# Sensorboard.net
KiCad netlist of a schematic drawn in EAGLE
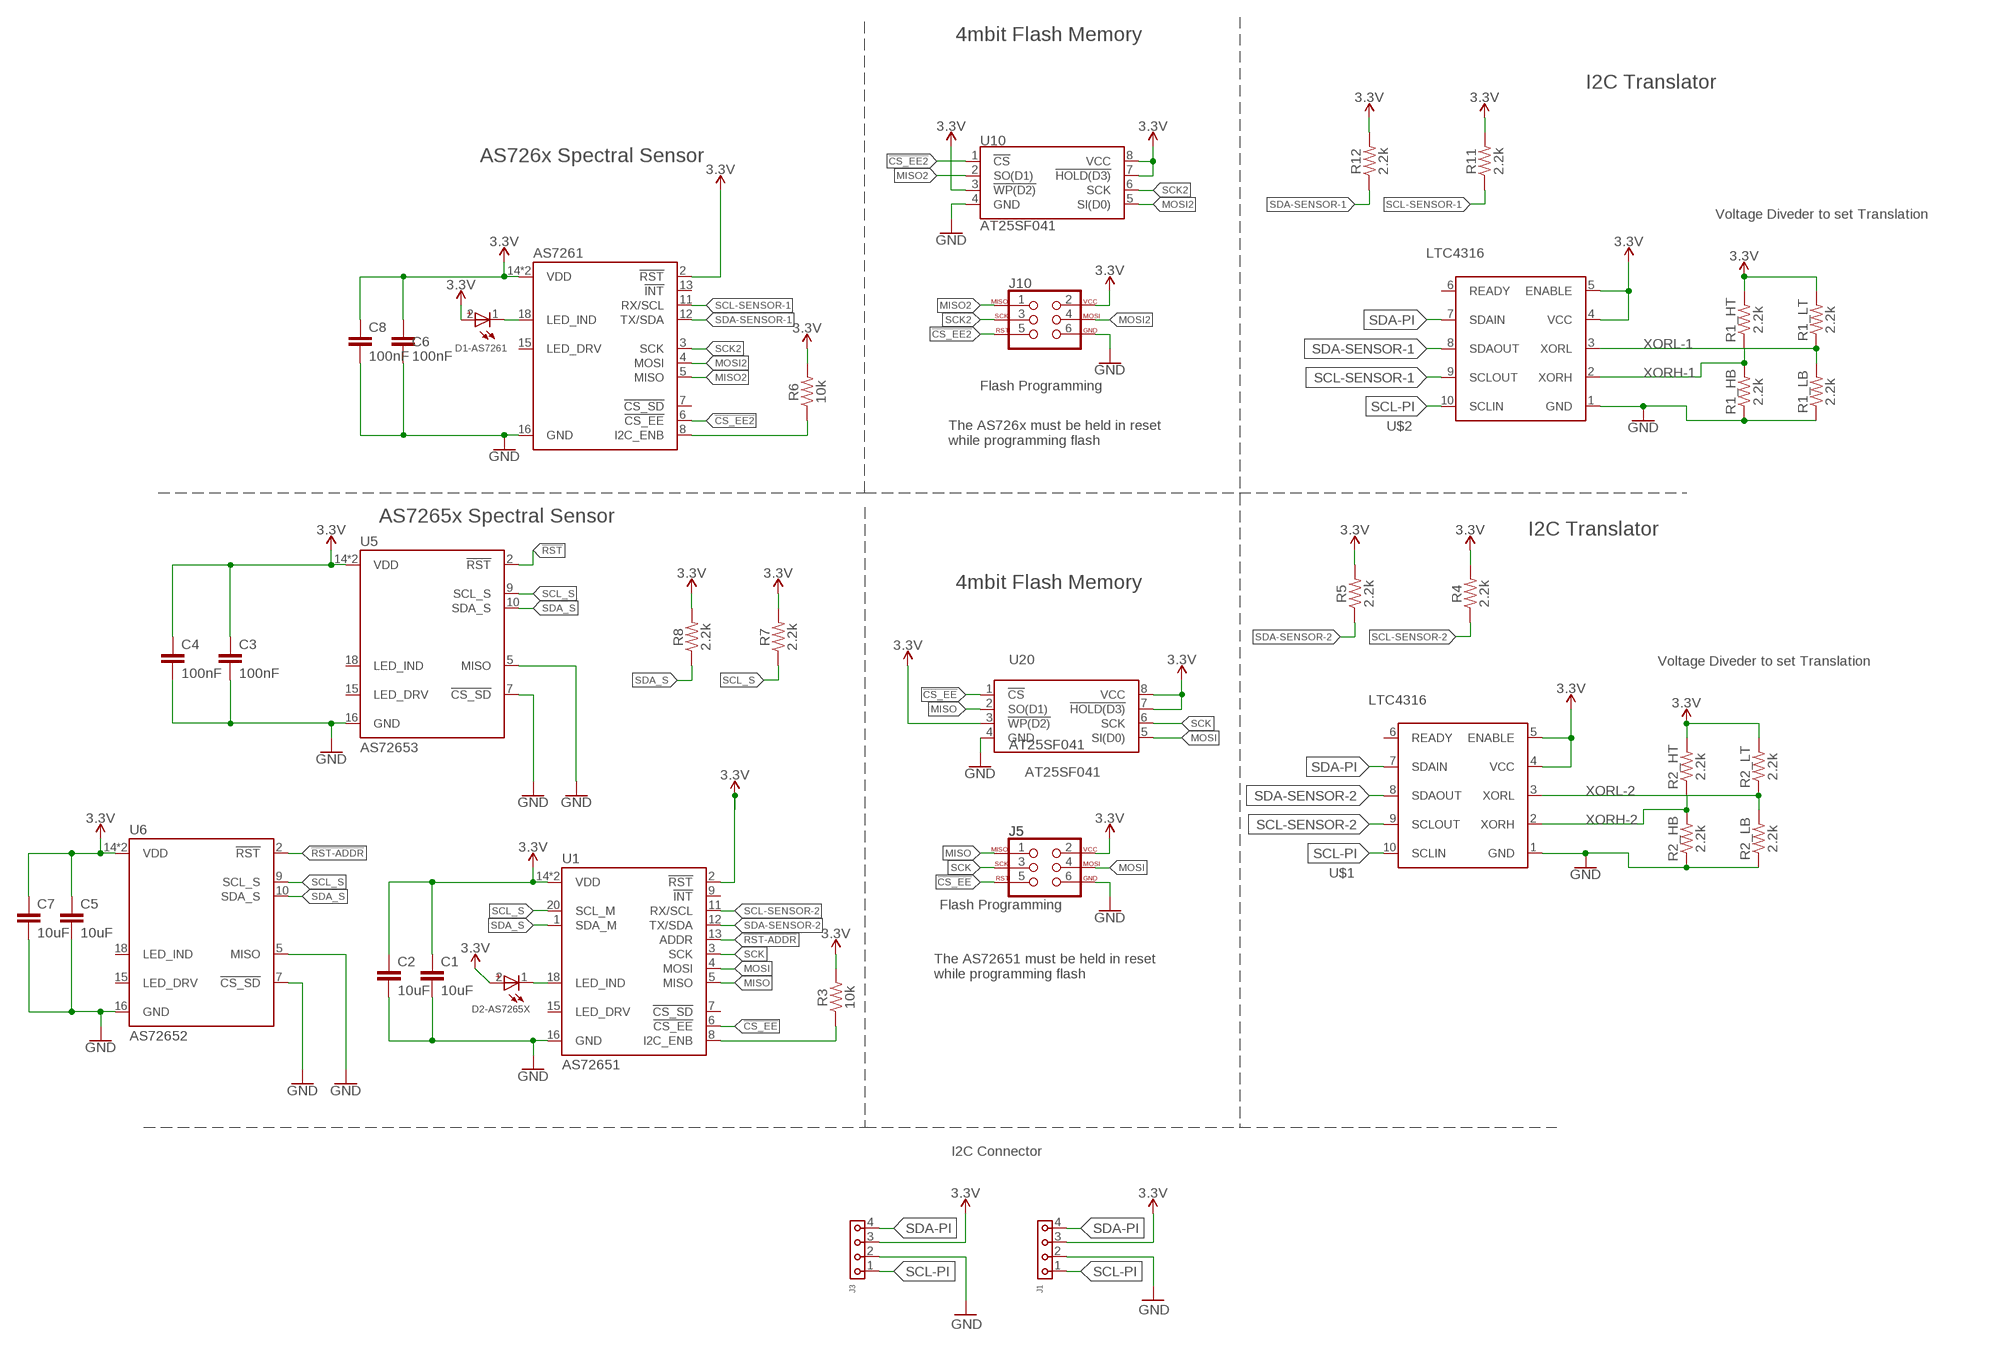
[diagram p0: schematic, sheet 1]

(export (version "E")
  (design (tool "Eeschema 10.0.6"))
  (components
    (comp (ref "AS7261")
      (value "IR")
      (footprint "eagle-import:LGA20")
      (libsource (lib "eagle-import") (part "AS726XIR"))
    )
    (comp (ref "C1")
      (value "10uF")
      (footprint "eagle-import:0603")
      (libsource (lib "eagle-import") (part "1.0UF-0603-16V-10%"))
    )
    (comp (ref "C2")
      (value "10uF")
      (footprint "eagle-import:0603")
      (libsource (lib "eagle-import") (part "10UF-0603-6.3V-20%"))
    )
    (comp (ref "C3")
      (value "100nF")
      (footprint "eagle-import:0603")
      (libsource (lib "eagle-import") (part "1.0UF-0603-16V-10%"))
    )
    (comp (ref "C4")
      (value "100nF")
      (footprint "eagle-import:0603")
      (libsource (lib "eagle-import") (part "10UF-0603-6.3V-20%"))
    )
    (comp (ref "C5")
      (value "10uF")
      (footprint "eagle-import:0603")
      (libsource (lib "eagle-import") (part "1.0UF-0603-16V-10%"))
    )
    (comp (ref "C6")
      (value "100nF")
      (footprint "eagle-import:0603")
      (libsource (lib "eagle-import") (part "1.0UF-0603-16V-10%"))
    )
    (comp (ref "C7")
      (value "10uF")
      (footprint "eagle-import:0603")
      (libsource (lib "eagle-import") (part "10UF-0603-6.3V-20%"))
    )
    (comp (ref "C8")
      (value "100nF")
      (footprint "eagle-import:0603")
      (libsource (lib "eagle-import") (part "10UF-0603-6.3V-20%"))
    )
    (comp (ref "D1-AS7261")
      (value "WL-SMCW_1206_150120RS75000")
      (footprint "eagle-import:WL-SMCW_1206")
      (libsource (lib "eagle-import") (part "WL-SMCW_1206_150120RS75000"))
    )
    (comp (ref "D2-AS7265X")
      (value "WL-SMCW_1206_150120RS75000")
      (footprint "eagle-import:WL-SMCW_1206")
      (libsource (lib "eagle-import") (part "WL-SMCW_1206_150120RS75000"))
    )
    (comp (ref "J1")
      (value "6130XX11821_61300411821")
      (footprint "eagle-import:61300411821")
      (libsource (lib "eagle-import") (part "6130XX11821_61300411821"))
    )
    (comp (ref "J3")
      (value "6130XX11821_61300411821")
      (footprint "eagle-import:61300411821")
      (libsource (lib "eagle-import") (part "6130XX11821_61300411821"))
    )
    (comp (ref "J5")
      (value "Flash Programming")
      (footprint "eagle-import:2X3_TEST_POINTS")
      (libsource (lib "eagle-import") (part "AVR_SPI_PROG_3X2TESTPOINTS"))
    )
    (comp (ref "J10")
      (value "Flash Programming")
      (footprint "eagle-import:2X3_TEST_POINTS")
      (libsource (lib "eagle-import") (part "AVR_SPI_PROG_3X2TESTPOINTS"))
    )
    (comp (ref "R1_HB")
      (value "2.2k")
      (footprint "eagle-import:0603")
      (libsource (lib "eagle-import") (part "2.2KOHM-0603-1/10W-1%"))
    )
    (comp (ref "R1_HT")
      (value "2.2k")
      (footprint "eagle-import:0603")
      (libsource (lib "eagle-import") (part "2.2KOHM-0603-1/10W-1%"))
    )
    (comp (ref "R1_LB")
      (value "2.2k")
      (footprint "eagle-import:0603")
      (libsource (lib "eagle-import") (part "2.2KOHM-0603-1/10W-1%"))
    )
    (comp (ref "R1_LT")
      (value "2.2k")
      (footprint "eagle-import:0603")
      (libsource (lib "eagle-import") (part "2.2KOHM-0603-1/10W-1%"))
    )
    (comp (ref "R2_HB")
      (value "2.2k")
      (footprint "eagle-import:0603")
      (libsource (lib "eagle-import") (part "2.2KOHM-0603-1/10W-1%"))
    )
    (comp (ref "R2_HT")
      (value "2.2k")
      (footprint "eagle-import:0603")
      (libsource (lib "eagle-import") (part "2.2KOHM-0603-1/10W-1%"))
    )
    (comp (ref "R2_LB")
      (value "2.2k")
      (footprint "eagle-import:0603")
      (libsource (lib "eagle-import") (part "2.2KOHM-0603-1/10W-1%"))
    )
    (comp (ref "R2_LT")
      (value "2.2k")
      (footprint "eagle-import:0603")
      (libsource (lib "eagle-import") (part "2.2KOHM-0603-1/10W-1%"))
    )
    (comp (ref "R3")
      (value "10k")
      (footprint "eagle-import:0603")
      (libsource (lib "eagle-import") (part "10KOHM-0603-1/10W-1%"))
    )
    (comp (ref "R4")
      (value "2.2k")
      (footprint "eagle-import:0603")
      (libsource (lib "eagle-import") (part "2.2KOHM-0603-1/10W-1%"))
    )
    (comp (ref "R5")
      (value "2.2k")
      (footprint "eagle-import:0603")
      (libsource (lib "eagle-import") (part "2.2KOHM-0603-1/10W-1%"))
    )
    (comp (ref "R6")
      (value "10k")
      (footprint "eagle-import:0603")
      (libsource (lib "eagle-import") (part "10KOHM-0603-1/10W-1%"))
    )
    (comp (ref "R7")
      (value "2.2k")
      (footprint "eagle-import:0603")
      (libsource (lib "eagle-import") (part "2.2KOHM-0603-1/10W-1%"))
    )
    (comp (ref "R8")
      (value "2.2k")
      (footprint "eagle-import:0603")
      (libsource (lib "eagle-import") (part "2.2KOHM-0603-1/10W-1%"))
    )
    (comp (ref "R11")
      (value "2.2k")
      (footprint "eagle-import:0603")
      (libsource (lib "eagle-import") (part "2.2KOHM-0603-1/10W-1%"))
    )
    (comp (ref "R12")
      (value "2.2k")
      (footprint "eagle-import:0603")
      (libsource (lib "eagle-import") (part "2.2KOHM-0603-1/10W-1%"))
    )
    (comp (ref "U$1")
      (value "LTC4316")
      (footprint "eagle-import:MS-PACKAGE")
      (libsource (lib "eagle-import") (part "LTC4316"))
    )
    (comp (ref "U$2")
      (value "LTC4316")
      (footprint "eagle-import:MS-PACKAGE")
      (libsource (lib "eagle-import") (part "LTC4316"))
    )
    (comp (ref "U1")
      (value "AS72651")
      (footprint "eagle-import:LGA20")
      (libsource (lib "eagle-import") (part "AS72651"))
    )
    (comp (ref "U5")
      (value "AS72653")
      (footprint "eagle-import:LGA20")
      (libsource (lib "eagle-import") (part "AS72653"))
    )
    (comp (ref "U6")
      (value "AS72652")
      (footprint "eagle-import:LGA20")
      (libsource (lib "eagle-import") (part "AS72652"))
    )
    (comp (ref "U10")
      (value "AT25SF041")
      (footprint "eagle-import:SO08")
      (libsource (lib "eagle-import") (part "AT25SF041"))
    )
    (comp (ref "U20")
      (value "AT25SF041")
      (footprint "eagle-import:SO08")
      (libsource (lib "eagle-import") (part "AT25SF041"))
    )
  )
  (nets
    (net (code "1") (name "/XORH-1") (class "Default")
      (node (ref "R1_HB") (pin "2") (pinfunction "2_2") (pintype "passive"))
      (node (ref "R1_HT") (pin "1") (pinfunction "1_1") (pintype "passive"))
      (node (ref "U$2") (pin "2") (pinfunction "XORH_2") (pintype "bidirectional"))
    )
    (net (code "2") (name "/XORH-2") (class "Default")
      (node (ref "R2_HB") (pin "2") (pinfunction "2_2") (pintype "passive"))
      (node (ref "R2_HT") (pin "1") (pinfunction "1_1") (pintype "passive"))
      (node (ref "U$1") (pin "2") (pinfunction "XORH_2") (pintype "bidirectional"))
    )
    (net (code "3") (name "/XORL-1") (class "Default")
      (node (ref "R1_LB") (pin "2") (pinfunction "2_2") (pintype "passive"))
      (node (ref "R1_LT") (pin "1") (pinfunction "1_1") (pintype "passive"))
      (node (ref "U$2") (pin "3") (pinfunction "XORL_3") (pintype "bidirectional"))
    )
    (net (code "4") (name "/XORL-2") (class "Default")
      (node (ref "R2_LB") (pin "2") (pinfunction "2_2") (pintype "passive"))
      (node (ref "R2_LT") (pin "1") (pinfunction "1_1") (pintype "passive"))
      (node (ref "U$1") (pin "3") (pinfunction "XORL_3") (pintype "bidirectional"))
    )
    (net (code "5") (name "/~{CS_EE2}") (class "Default")
      (node (ref "AS7261") (pin "6") (pinfunction "~{CS_EE}_6") (pintype "bidirectional"))
      (node (ref "J10") (pin "5") (pinfunction "5_5") (pintype "passive"))
      (node (ref "U10") (pin "1") (pinfunction "~{CS}_1") (pintype "bidirectional"))
    )
    (net (code "6") (name "/~{CS_EE}") (class "Default")
      (node (ref "J5") (pin "5") (pinfunction "5_5") (pintype "passive"))
      (node (ref "U1") (pin "6") (pinfunction "~{CS_EE}_6") (pintype "bidirectional"))
      (node (ref "U20") (pin "1") (pinfunction "~{CS}_1") (pintype "bidirectional"))
    )
    (net (code "7") (name "/~{RST-ADDR}") (class "Default")
      (node (ref "U1") (pin "13") (pinfunction "ADDR_13") (pintype "bidirectional"))
      (node (ref "U6") (pin "2") (pinfunction "~{RST}_2") (pintype "bidirectional"))
    )
    (net (code "8") (name "/~{RST}") (class "Default")
      (node (ref "U5") (pin "2") (pinfunction "~{RST}_2") (pintype "bidirectional"))
    )
    (net (code "9") (name "3.3V") (class "Default")
      (node (ref "AS7261") (pin "14") (pinfunction "VDD_14") (pintype "bidirectional"))
      (node (ref "AS7261") (pin "17") (pinfunction "VDD_17") (pintype "bidirectional"))
      (node (ref "AS7261") (pin "2") (pinfunction "~{RST}_2") (pintype "bidirectional"))
      (node (ref "C1") (pin "1") (pinfunction "1_1") (pintype "passive"))
      (node (ref "C2") (pin "1") (pinfunction "1_1") (pintype "passive"))
      (node (ref "C3") (pin "1") (pinfunction "1_1") (pintype "passive"))
      (node (ref "C4") (pin "1") (pinfunction "1_1") (pintype "passive"))
      (node (ref "C5") (pin "1") (pinfunction "1_1") (pintype "passive"))
      (node (ref "C6") (pin "1") (pinfunction "1_1") (pintype "passive"))
      (node (ref "C7") (pin "1") (pinfunction "1_1") (pintype "passive"))
      (node (ref "C8") (pin "1") (pinfunction "1_1") (pintype "passive"))
      (node (ref "D1-AS7261") (pin "2") (pinfunction "+_2") (pintype "passive"))
      (node (ref "D2-AS7265X") (pin "2") (pinfunction "+_2") (pintype "passive"))
      (node (ref "J1") (pin "3") (pinfunction "3_3") (pintype "passive"))
      (node (ref "J10") (pin "2") (pinfunction "2_2") (pintype "passive"))
      (node (ref "J3") (pin "3") (pinfunction "3_3") (pintype "passive"))
      (node (ref "J5") (pin "2") (pinfunction "2_2") (pintype "passive"))
      (node (ref "R11") (pin "2") (pinfunction "2_2") (pintype "passive"))
      (node (ref "R12") (pin "2") (pinfunction "2_2") (pintype "passive"))
      (node (ref "R1_HT") (pin "2") (pinfunction "2_2") (pintype "passive"))
      (node (ref "R1_LT") (pin "2") (pinfunction "2_2") (pintype "passive"))
      (node (ref "R2_HT") (pin "2") (pinfunction "2_2") (pintype "passive"))
      (node (ref "R2_LT") (pin "2") (pinfunction "2_2") (pintype "passive"))
      (node (ref "R3") (pin "2") (pinfunction "2_2") (pintype "passive"))
      (node (ref "R4") (pin "2") (pinfunction "2_2") (pintype "passive"))
      (node (ref "R5") (pin "2") (pinfunction "2_2") (pintype "passive"))
      (node (ref "R6") (pin "2") (pinfunction "2_2") (pintype "passive"))
      (node (ref "R7") (pin "2") (pinfunction "2_2") (pintype "passive"))
      (node (ref "R8") (pin "2") (pinfunction "2_2") (pintype "passive"))
      (node (ref "U$1") (pin "4") (pinfunction "VCC_4") (pintype "bidirectional"))
      (node (ref "U$1") (pin "5") (pinfunction "ENABLE_5") (pintype "bidirectional"))
      (node (ref "U$2") (pin "4") (pinfunction "VCC_4") (pintype "bidirectional"))
      (node (ref "U$2") (pin "5") (pinfunction "ENABLE_5") (pintype "bidirectional"))
      (node (ref "U1") (pin "14") (pinfunction "VDD_14") (pintype "bidirectional"))
      (node (ref "U1") (pin "17") (pinfunction "VDD_17") (pintype "bidirectional"))
      (node (ref "U1") (pin "2") (pinfunction "~{RST}_2") (pintype "bidirectional"))
      (node (ref "U10") (pin "3") (pinfunction "~{WP(D2})_3") (pintype "bidirectional"))
      (node (ref "U10") (pin "7") (pinfunction "~{HOLD(D3})_7") (pintype "bidirectional"))
      (node (ref "U10") (pin "8") (pinfunction "VCC_8") (pintype "bidirectional"))
      (node (ref "U20") (pin "3") (pinfunction "~{WP(D2})_3") (pintype "bidirectional"))
      (node (ref "U20") (pin "7") (pinfunction "~{HOLD(D3})_7") (pintype "bidirectional"))
      (node (ref "U20") (pin "8") (pinfunction "VCC_8") (pintype "bidirectional"))
      (node (ref "U5") (pin "14") (pinfunction "VDD_14") (pintype "bidirectional"))
      (node (ref "U5") (pin "17") (pinfunction "VDD_17") (pintype "bidirectional"))
      (node (ref "U6") (pin "14") (pinfunction "VDD_14") (pintype "bidirectional"))
      (node (ref "U6") (pin "17") (pinfunction "VDD_17") (pintype "bidirectional"))
    )
    (net (code "10") (name "GND") (class "Default")
      (node (ref "AS7261") (pin "16") (pinfunction "GND_16") (pintype "bidirectional"))
      (node (ref "C1") (pin "2") (pinfunction "2_2") (pintype "passive"))
      (node (ref "C2") (pin "2") (pinfunction "2_2") (pintype "passive"))
      (node (ref "C3") (pin "2") (pinfunction "2_2") (pintype "passive"))
      (node (ref "C4") (pin "2") (pinfunction "2_2") (pintype "passive"))
      (node (ref "C5") (pin "2") (pinfunction "2_2") (pintype "passive"))
      (node (ref "C6") (pin "2") (pinfunction "2_2") (pintype "passive"))
      (node (ref "C7") (pin "2") (pinfunction "2_2") (pintype "passive"))
      (node (ref "C8") (pin "2") (pinfunction "2_2") (pintype "passive"))
      (node (ref "J1") (pin "2") (pinfunction "2_2") (pintype "passive"))
      (node (ref "J10") (pin "6") (pinfunction "6_6") (pintype "passive"))
      (node (ref "J3") (pin "2") (pinfunction "2_2") (pintype "passive"))
      (node (ref "J5") (pin "6") (pinfunction "6_6") (pintype "passive"))
      (node (ref "R1_HB") (pin "1") (pinfunction "1_1") (pintype "passive"))
      (node (ref "R1_LB") (pin "1") (pinfunction "1_1") (pintype "passive"))
      (node (ref "R2_HB") (pin "1") (pinfunction "1_1") (pintype "passive"))
      (node (ref "R2_LB") (pin "1") (pinfunction "1_1") (pintype "passive"))
      (node (ref "U$1") (pin "1") (pinfunction "GND_1") (pintype "bidirectional"))
      (node (ref "U$2") (pin "1") (pinfunction "GND_1") (pintype "bidirectional"))
      (node (ref "U1") (pin "16") (pinfunction "GND_16") (pintype "bidirectional"))
      (node (ref "U10") (pin "4") (pinfunction "GND_4") (pintype "bidirectional"))
      (node (ref "U20") (pin "4") (pinfunction "GND_4") (pintype "bidirectional"))
      (node (ref "U5") (pin "16") (pinfunction "GND_16") (pintype "bidirectional"))
      (node (ref "U5") (pin "5") (pinfunction "MISO_5") (pintype "bidirectional"))
      (node (ref "U5") (pin "7") (pinfunction "~{CS_SD}_7") (pintype "bidirectional"))
      (node (ref "U6") (pin "16") (pinfunction "GND_16") (pintype "bidirectional"))
      (node (ref "U6") (pin "5") (pinfunction "MISO_5") (pintype "bidirectional"))
      (node (ref "U6") (pin "7") (pinfunction "~{CS_SD}_7") (pintype "bidirectional"))
    )
    (net (code "11") (name "MISO") (class "Default")
      (node (ref "J5") (pin "1") (pinfunction "1_1") (pintype "passive"))
      (node (ref "U1") (pin "5") (pinfunction "MISO_5") (pintype "bidirectional"))
      (node (ref "U20") (pin "2") (pinfunction "SO(D1)_2") (pintype "bidirectional"))
    )
    (net (code "12") (name "MISO2") (class "Default")
      (node (ref "AS7261") (pin "5") (pinfunction "MISO_5") (pintype "bidirectional"))
      (node (ref "J10") (pin "1") (pinfunction "1_1") (pintype "passive"))
      (node (ref "U10") (pin "2") (pinfunction "SO(D1)_2") (pintype "bidirectional"))
    )
    (net (code "13") (name "MOSI") (class "Default")
      (node (ref "J5") (pin "4") (pinfunction "4_4") (pintype "passive"))
      (node (ref "U1") (pin "4") (pinfunction "MOSI_4") (pintype "bidirectional"))
      (node (ref "U20") (pin "5") (pinfunction "SI(D0)_5") (pintype "bidirectional"))
    )
    (net (code "14") (name "MOSI2") (class "Default")
      (node (ref "AS7261") (pin "4") (pinfunction "MOSI_4") (pintype "bidirectional"))
      (node (ref "J10") (pin "4") (pinfunction "4_4") (pintype "passive"))
      (node (ref "U10") (pin "5") (pinfunction "SI(D0)_5") (pintype "bidirectional"))
    )
    (net (code "15") (name "Net-(AS7261-I2C_ENB)") (class "Default")
      (node (ref "AS7261") (pin "8") (pinfunction "I2C_ENB_8") (pintype "bidirectional"))
      (node (ref "R6") (pin "1") (pinfunction "1_1") (pintype "passive"))
    )
    (net (code "16") (name "Net-(AS7261-LED_IND)") (class "Default")
      (node (ref "AS7261") (pin "18") (pinfunction "LED_IND_18") (pintype "bidirectional"))
      (node (ref "D1-AS7261") (pin "1") (pinfunction "-_1") (pintype "passive"))
    )
    (net (code "17") (name "Net-(D2-AS7265X--)") (class "Default")
      (node (ref "D2-AS7265X") (pin "1") (pinfunction "-_1") (pintype "passive"))
      (node (ref "U1") (pin "18") (pinfunction "LED_IND_18") (pintype "bidirectional"))
    )
    (net (code "18") (name "Net-(U1-I2C_ENB)") (class "Default")
      (node (ref "R3") (pin "1") (pinfunction "1_1") (pintype "passive"))
      (node (ref "U1") (pin "8") (pinfunction "I2C_ENB_8") (pintype "bidirectional"))
    )
    (net (code "19") (name "SCK") (class "Default")
      (node (ref "J5") (pin "3") (pinfunction "3_3") (pintype "passive"))
      (node (ref "U1") (pin "3") (pinfunction "SCK_3") (pintype "bidirectional"))
      (node (ref "U20") (pin "6") (pinfunction "SCK_6") (pintype "bidirectional"))
    )
    (net (code "20") (name "SCK2") (class "Default")
      (node (ref "AS7261") (pin "3") (pinfunction "SCK_3") (pintype "bidirectional"))
      (node (ref "J10") (pin "3") (pinfunction "3_3") (pintype "passive"))
      (node (ref "U10") (pin "6") (pinfunction "SCK_6") (pintype "bidirectional"))
    )
    (net (code "21") (name "SCL-PI") (class "Default")
      (node (ref "J1") (pin "1") (pinfunction "1_1") (pintype "passive"))
      (node (ref "J3") (pin "1") (pinfunction "1_1") (pintype "passive"))
      (node (ref "U$1") (pin "10") (pinfunction "SCLIN_10") (pintype "bidirectional"))
      (node (ref "U$2") (pin "10") (pinfunction "SCLIN_10") (pintype "bidirectional"))
    )
    (net (code "22") (name "SCL-SENSOR-1") (class "Default")
      (node (ref "AS7261") (pin "11") (pinfunction "RX/SCL_11") (pintype "bidirectional"))
      (node (ref "R11") (pin "1") (pinfunction "1_1") (pintype "passive"))
      (node (ref "U$2") (pin "9") (pinfunction "SCLOUT_9") (pintype "bidirectional"))
    )
    (net (code "23") (name "SCL-SENSOR-2") (class "Default")
      (node (ref "R4") (pin "1") (pinfunction "1_1") (pintype "passive"))
      (node (ref "U$1") (pin "9") (pinfunction "SCLOUT_9") (pintype "bidirectional"))
      (node (ref "U1") (pin "11") (pinfunction "RX/SCL_11") (pintype "bidirectional"))
    )
    (net (code "24") (name "SCL_S") (class "Default")
      (node (ref "R7") (pin "1") (pinfunction "1_1") (pintype "passive"))
      (node (ref "U1") (pin "20") (pinfunction "SCL_M_20") (pintype "bidirectional"))
      (node (ref "U5") (pin "9") (pinfunction "SCL_S_9") (pintype "bidirectional"))
      (node (ref "U6") (pin "9") (pinfunction "SCL_S_9") (pintype "bidirectional"))
    )
    (net (code "25") (name "SDA-PI") (class "Default")
      (node (ref "J1") (pin "4") (pinfunction "4_4") (pintype "passive"))
      (node (ref "J3") (pin "4") (pinfunction "4_4") (pintype "passive"))
      (node (ref "U$1") (pin "7") (pinfunction "SDAIN_7") (pintype "bidirectional"))
      (node (ref "U$2") (pin "7") (pinfunction "SDAIN_7") (pintype "bidirectional"))
    )
    (net (code "26") (name "SDA-SENSOR-1") (class "Default")
      (node (ref "AS7261") (pin "12") (pinfunction "TX/SDA_12") (pintype "bidirectional"))
      (node (ref "R12") (pin "1") (pinfunction "1_1") (pintype "passive"))
      (node (ref "U$2") (pin "8") (pinfunction "SDAOUT_8") (pintype "bidirectional"))
    )
    (net (code "27") (name "SDA-SENSOR-2") (class "Default")
      (node (ref "R5") (pin "1") (pinfunction "1_1") (pintype "passive"))
      (node (ref "U$1") (pin "8") (pinfunction "SDAOUT_8") (pintype "bidirectional"))
      (node (ref "U1") (pin "12") (pinfunction "TX/SDA_12") (pintype "bidirectional"))
    )
    (net (code "28") (name "SDA_S") (class "Default")
      (node (ref "R8") (pin "1") (pinfunction "1_1") (pintype "passive"))
      (node (ref "U1") (pin "1") (pinfunction "SDA_M_1") (pintype "bidirectional"))
      (node (ref "U5") (pin "10") (pinfunction "SDA_S_10") (pintype "bidirectional"))
      (node (ref "U6") (pin "10") (pinfunction "SDA_S_10") (pintype "bidirectional"))
    )
    (net (code "29") (name "unconnected-(AS7261-LED_DRV-Pad15)") (class "Default")
      (node (ref "AS7261") (pin "15") (pinfunction "LED_DRV_15") (pintype "bidirectional"))
    )
    (net (code "30") (name "unconnected-(AS7261-~{CS_SD}-Pad7)") (class "Default")
      (node (ref "AS7261") (pin "7") (pinfunction "~{CS_SD}_7") (pintype "bidirectional"))
    )
    (net (code "31") (name "unconnected-(AS7261-~{INT}-Pad13)") (class "Default")
      (node (ref "AS7261") (pin "13") (pinfunction "~{INT}_13") (pintype "bidirectional"))
    )
    (net (code "32") (name "unconnected-(U$1-READY-Pad6)") (class "Default")
      (node (ref "U$1") (pin "6") (pinfunction "READY_6") (pintype "bidirectional"))
    )
    (net (code "33") (name "unconnected-(U$2-READY-Pad6)") (class "Default")
      (node (ref "U$2") (pin "6") (pinfunction "READY_6") (pintype "bidirectional"))
    )
    (net (code "34") (name "unconnected-(U1-LED_DRV-Pad15)") (class "Default")
      (node (ref "U1") (pin "15") (pinfunction "LED_DRV_15") (pintype "bidirectional"))
    )
    (net (code "35") (name "unconnected-(U1-~{CS_SD}-Pad7)") (class "Default")
      (node (ref "U1") (pin "7") (pinfunction "~{CS_SD}_7") (pintype "bidirectional"))
    )
    (net (code "36") (name "unconnected-(U1-~{INT}-Pad9)") (class "Default")
      (node (ref "U1") (pin "9") (pinfunction "~{INT}_9") (pintype "bidirectional"))
    )
    (net (code "37") (name "unconnected-(U5-LED_DRV-Pad15)") (class "Default")
      (node (ref "U5") (pin "15") (pinfunction "LED_DRV_15") (pintype "bidirectional"))
    )
    (net (code "38") (name "unconnected-(U5-LED_IND-Pad18)") (class "Default")
      (node (ref "U5") (pin "18") (pinfunction "LED_IND_18") (pintype "bidirectional"))
    )
    (net (code "39") (name "unconnected-(U6-LED_DRV-Pad15)") (class "Default")
      (node (ref "U6") (pin "15") (pinfunction "LED_DRV_15") (pintype "bidirectional"))
    )
    (net (code "40") (name "unconnected-(U6-LED_IND-Pad18)") (class "Default")
      (node (ref "U6") (pin "18") (pinfunction "LED_IND_18") (pintype "bidirectional"))
    )
  )
)
